# SAML21_Xplained_Pro_current_measurement_.net
KiCad netlist of a schematic drawn in Altium Designer
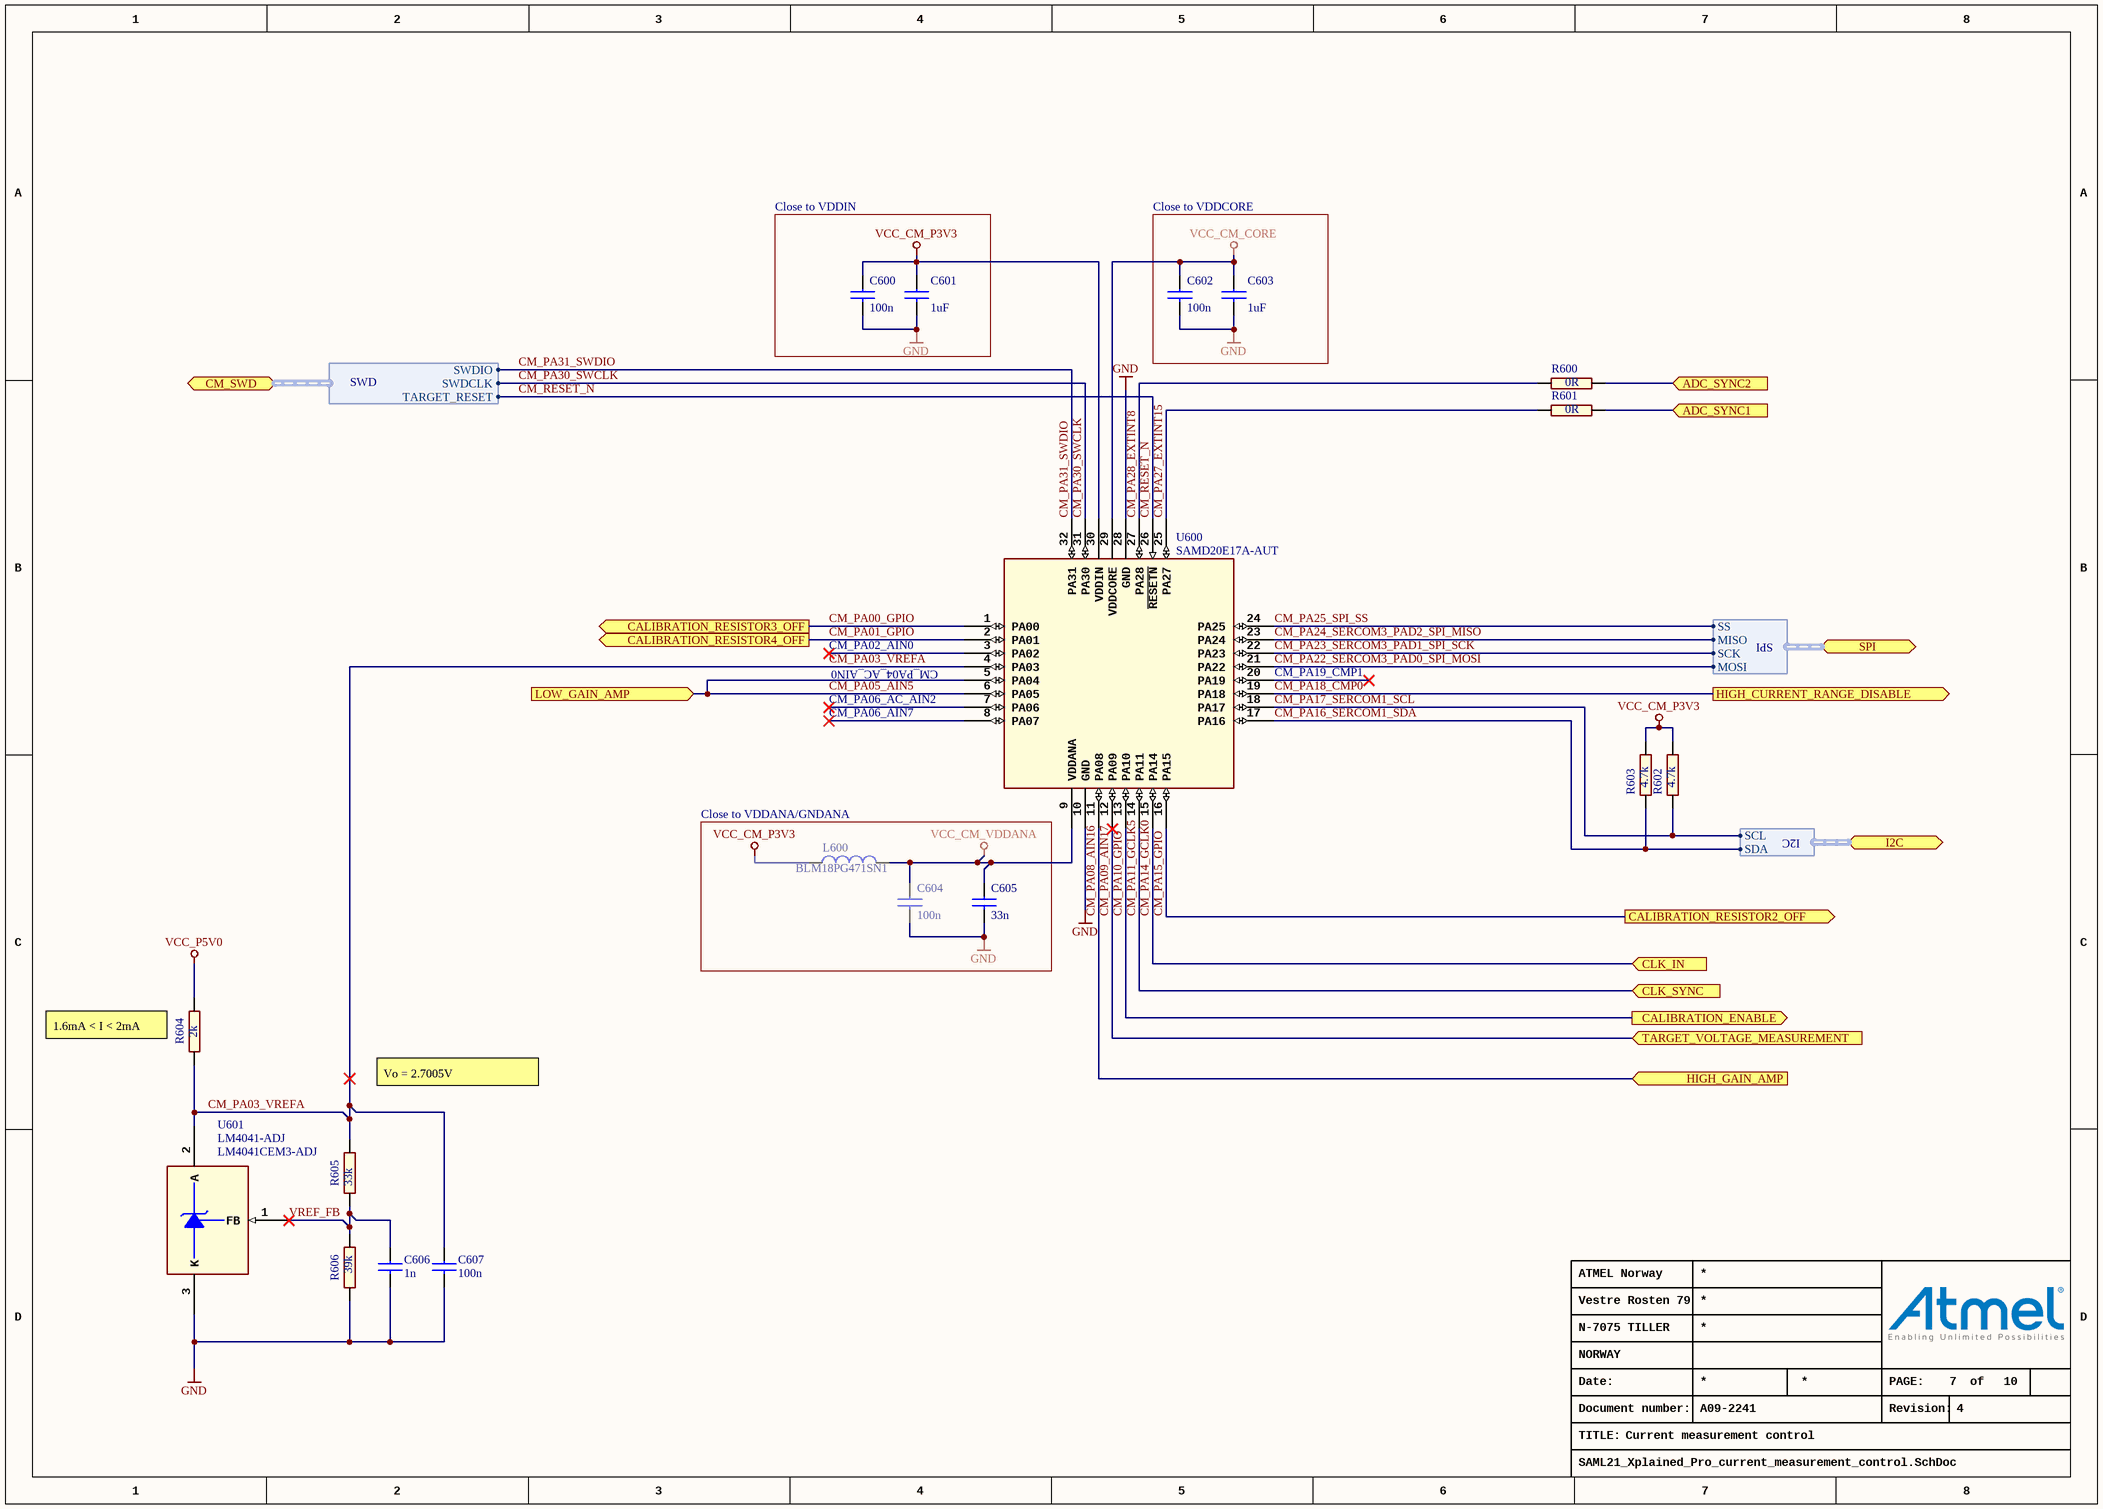
[diagram p0: SAML21_Xplained_Pro_current_measurement_control.SchDoc]

(export (version "E")
  (design (tool "Eeschema 10.0.6"))
  (components
    (comp (ref "C600")
      (value "100n")
      (footprint "AP1-00053")
      (description "Ceramic capacitor, SMD 0402, X7R, 16V, +/-10%")
      (fields (field (name "TOLERANCE") "16V, +/-10%") (field (name "MANUFACTURER") "Kemet"))
      (libsource (lib "AltiumDbLib") (part "CAP-NONPOL"))
    )
    (comp (ref "C601")
      (value "1uF")
      (footprint "AP1-00117")
      (description "Ceramic capacitor, SMD 0603, X5R, 25V, ±10%")
      (fields (field (name "TOLERANCE") "±10%") (field (name "MANUFACTURER") "Murata"))
      (libsource (lib "AltiumDbLib") (part "CAP-NONPOL"))
    )
    (comp (ref "C602")
      (value "100n")
      (footprint "AP1-00053")
      (description "Ceramic capacitor, SMD 0402, X7R, 16V, +/-10%")
      (fields (field (name "TOLERANCE") "16V, +/-10%") (field (name "MANUFACTURER") "Kemet"))
      (libsource (lib "AltiumDbLib") (part "CAP-NONPOL"))
    )
    (comp (ref "C603")
      (value "1uF")
      (footprint "AP1-00117")
      (description "Ceramic capacitor, SMD 0603, X5R, 25V, ±10%")
      (fields (field (name "TOLERANCE") "±10%") (field (name "MANUFACTURER") "Murata"))
      (libsource (lib "AltiumDbLib") (part "CAP-NONPOL"))
    )
    (comp (ref "C604")
      (value "100n")
      (footprint "AP1-00053")
      (description "Ceramic capacitor, SMD 0402, X7R, 16V, +/-10%")
      (fields (field (name "TOLERANCE") "16V, +/-10%") (field (name "MANUFACTURER") "Kemet"))
      (libsource (lib "AltiumDbLib") (part "CAP-NONPOL"))
    )
    (comp (ref "C605")
      (value "33n")
      (footprint "AP1-00053")
      (description "Ceramic capacitor, SMD 0402, X7R, 25V, ±10%")
      (fields (field (name "TOLERANCE") "±10%(K)") (field (name "MANUFACTURER") "Murata"))
      (libsource (lib "AltiumDbLib") (part "CAP-NONPOL"))
    )
    (comp (ref "C606")
      (value "1n")
      (footprint "AP1-00053")
      (description "Ceramic capacitor, SMD 0402, X7R, 50V, +/-10%")
      (fields (field (name "TOLERANCE") "50V, +/-10%") (field (name "Comment") "CAP-NONPOL"))
      (libsource (lib "AltiumDbLib") (part "CAP-NONPOL"))
    )
    (comp (ref "C607")
      (value "100n")
      (footprint "AP1-00053")
      (description "Ceramic capacitor, SMD 0402, X7R, 16V, +/-10%")
      (fields (field (name "TOLERANCE") "16V, +/-10%") (field (name "MANUFACTURER") "Kemet"))
      (libsource (lib "AltiumDbLib") (part "CAP-NONPOL"))
    )
    (comp (ref "L600")
      (value "BLM18PG471SN1")
      (footprint "AP3-00005")
      (description "SMD RF inductor 0603. Z=470Ohm (@100MHz), Max R(dc)=0.65Ohm, Max current=1A")
      (fields (field (name "TOLERANCE") "±25%") (field (name "MANUFACTURER") "Murata"))
      (libsource (lib "AltiumDbLib") (part "INDUCTOR"))
    )
    (comp (ref "R600")
      (value "0R")
      (footprint "AP2-00011")
      (description "RES 0.0 OHM 1/16W 0402 SMD")
      (fields (field (name "TOLERANCE") "1 %") (field (name "MANUFACTURER") "(n/a)"))
      (libsource (lib "") (part "R2_1"))
    )
    (comp (ref "R601")
      (value "0R")
      (footprint "AP2-00011")
      (description "RES 0.0 OHM 1/16W 0402 SMD")
      (fields (field (name "TOLERANCE") "1 %") (field (name "MANUFACTURER") "(n/a)"))
      (libsource (lib "") (part "R2_1"))
    )
    (comp (ref "R602")
      (value "4.7k")
      (footprint "AP2-00011")
      (description "Thick film resistor, SMD 0402, 1/16W, 1%")
      (fields (field (name "TOLERANCE") "1 %") (field (name "Comment") "R2"))
      (libsource (lib "") (part "R2_1"))
    )
    (comp (ref "R603")
      (value "4.7k")
      (footprint "AP2-00011")
      (description "Thick film resistor, SMD 0402, 1/16W, 1%")
      (fields (field (name "TOLERANCE") "1 %") (field (name "Comment") "R2"))
      (libsource (lib "") (part "R2_1"))
    )
    (comp (ref "R604")
      (value "2k")
      (footprint "AP2-00011")
      (description "Thick film resistor, SMD 0402, 1/16W, 1%")
      (fields (field (name "TOLERANCE") "1 %") (field (name "Comment") "R2"))
      (libsource (lib "AltiumDbLib") (part "R2"))
    )
    (comp (ref "R605")
      (value "33k")
      (footprint "AP2-00011")
      (description "Thick film resistor, SMD 0402, 1/16W, 1%")
      (fields (field (name "TOLERANCE") "1 %") (field (name "Comment") "R2"))
      (libsource (lib "AltiumDbLib") (part "R2"))
    )
    (comp (ref "R606")
      (value "39k")
      (footprint "AP2-00011")
      (description "Thick film resistor, SMD 0402, 1/16W, 1%")
      (fields (field (name "TOLERANCE") "1 %") (field (name "Comment") "R2"))
      (libsource (lib "AltiumDbLib") (part "R2"))
    )
    (comp (ref "U600")
      (value "SAMD20E17A-AUT")
      (footprint "AP6-00061")
      (description "Atmel 32bit RISC MCU 32 pin")
      (fields (field (name "MANUFACTURER") "ATMEL") (field (name "MPN") "ATSAMD20E17A-AUT"))
      (libsource (lib "AltiumDbLib") (part "SAMD20E"))
    )
    (comp (ref "U601")
      (value "LM4041-ADJ")
      (footprint "AP5-00002")
      (description "Adjustable shunt voltage regulator, 1.24 to 10V out")
      (fields
        (field (name "ALTIUM_VALUE") "LM4041CEM3-ADJ")
        (field (name "MANUFACTURER") "National Semiconductor")
        (field (name "MPN") "LM4041CEM3-ADJ")
      )
      (libsource (lib "AltiumDbLib") (part "LM4041-ADJ"))
    )
  )
  (nets
    (net (code "4") (name "/ADC_SYNC1") (class "Default")
      (node (ref "R601") (pin "2") (pinfunction "2_2") (pintype "passive"))
    )
    (net (code "5") (name "/ADC_SYNC2") (class "Default")
      (node (ref "R600") (pin "2") (pinfunction "2_2") (pintype "passive"))
    )
    (net (code "6") (name "/CM_PA00_GPIO") (class "Default")
      (node (ref "U600") (pin "1") (pinfunction "PA00_1") (pintype "bidirectional"))
    )
    (net (code "7") (name "/CM_PA01_GPIO") (class "Default")
      (node (ref "U600") (pin "2") (pinfunction "PA01_2") (pintype "bidirectional"))
    )
    (net (code "8") (name "/CM_PA03_VREFA") (class "Default")
      (node (ref "C607") (pin "1") (pinfunction "1_1") (pintype "passive"))
      (node (ref "R604") (pin "1") (pinfunction "1_1") (pintype "passive"))
      (node (ref "R605") (pin "2") (pinfunction "2_2") (pintype "passive"))
      (node (ref "U600") (pin "4") (pinfunction "PA03_4") (pintype "bidirectional"))
      (node (ref "U601") (pin "2") (pinfunction "A_2") (pintype "power_in"))
    )
    (net (code "9") (name "/CM_PA05_AIN5") (class "Default")
      (node (ref "U600") (pin "5") (pinfunction "PA04_5") (pintype "bidirectional"))
      (node (ref "U600") (pin "6") (pinfunction "PA05_6") (pintype "bidirectional"))
    )
    (net (code "10") (name "/CM_PA08_AIN16") (class "Default")
      (node (ref "U600") (pin "11") (pinfunction "PA08_11") (pintype "bidirectional"))
    )
    (net (code "11") (name "/CM_PA09_AIN17") (class "Default")
      (node (ref "U600") (pin "12") (pinfunction "PA09_12") (pintype "bidirectional+no_connect"))
    )
    (net (code "12") (name "/CM_PA10_GPIO") (class "Default")
      (node (ref "U600") (pin "13") (pinfunction "PA10_13") (pintype "bidirectional"))
    )
    (net (code "13") (name "/CM_PA11_GCLK5") (class "Default")
      (node (ref "U600") (pin "14") (pinfunction "PA11_14") (pintype "bidirectional"))
    )
    (net (code "14") (name "/CM_PA14_GCLK0") (class "Default")
      (node (ref "U600") (pin "15") (pinfunction "PA14_15") (pintype "bidirectional"))
    )
    (net (code "15") (name "/CM_PA15_GPIO") (class "Default")
      (node (ref "U600") (pin "16") (pinfunction "PA15_16") (pintype "bidirectional"))
    )
    (net (code "16") (name "/CM_PA16_SERCOM1_SDA") (class "Default")
      (node (ref "R603") (pin "1") (pinfunction "1_1") (pintype "passive"))
      (node (ref "U600") (pin "17") (pinfunction "PA16_17") (pintype "bidirectional"))
    )
    (net (code "17") (name "/CM_PA17_SERCOM1_SCL") (class "Default")
      (node (ref "R602") (pin "1") (pinfunction "1_1") (pintype "passive"))
      (node (ref "U600") (pin "18") (pinfunction "PA17_18") (pintype "bidirectional"))
    )
    (net (code "18") (name "/CM_PA18_CMP0") (class "Default")
      (node (ref "U600") (pin "19") (pinfunction "PA18_19") (pintype "bidirectional"))
    )
    (net (code "19") (name "/CM_PA22_SERCOM3_PAD0_SPI_MOSI") (class "Default")
      (node (ref "U600") (pin "21") (pinfunction "PA22_21") (pintype "bidirectional"))
    )
    (net (code "20") (name "/CM_PA23_SERCOM3_PAD1_SPI_SCK") (class "Default")
      (node (ref "U600") (pin "22") (pinfunction "PA23_22") (pintype "bidirectional"))
    )
    (net (code "21") (name "/CM_PA24_SERCOM3_PAD2_SPI_MISO") (class "Default")
      (node (ref "U600") (pin "23") (pinfunction "PA24_23") (pintype "bidirectional"))
    )
    (net (code "22") (name "/CM_PA25_SPI_SS") (class "Default")
      (node (ref "U600") (pin "24") (pinfunction "PA25_24") (pintype "bidirectional"))
    )
    (net (code "23") (name "/CM_PA27_EXTINT15") (class "Default")
      (node (ref "R601") (pin "1") (pinfunction "1_1") (pintype "passive"))
      (node (ref "U600") (pin "25") (pinfunction "PA27_25") (pintype "bidirectional"))
    )
    (net (code "24") (name "/CM_PA28_EXTINT8") (class "Default")
      (node (ref "R600") (pin "1") (pinfunction "1_1") (pintype "passive"))
      (node (ref "U600") (pin "27") (pinfunction "PA28_27") (pintype "bidirectional"))
    )
    (net (code "25") (name "/CM_PA30_SWCLK") (class "Default")
      (node (ref "U600") (pin "31") (pinfunction "PA30_31") (pintype "bidirectional"))
    )
    (net (code "26") (name "/CM_PA31_SWDIO") (class "Default")
      (node (ref "U600") (pin "32") (pinfunction "PA31_32") (pintype "bidirectional"))
    )
    (net (code "27") (name "/CM_RESET_N") (class "Default")
      (node (ref "U600") (pin "26") (pinfunction "~{RESETN}_26") (pintype "input"))
    )
    (net (code "28") (name "/VREF_FB") (class "Default")
      (node (ref "C606") (pin "1") (pinfunction "1_1") (pintype "passive"))
      (node (ref "R605") (pin "1") (pinfunction "1_1") (pintype "passive"))
      (node (ref "R606") (pin "2") (pinfunction "2_2") (pintype "passive"))
      (node (ref "U601") (pin "1") (pinfunction "FB_1") (pintype "input"))
    )
    (net (code "32") (name "GND") (class "Default")
      (node (ref "C600") (pin "2") (pinfunction "2_2") (pintype "passive"))
      (node (ref "C601") (pin "2") (pinfunction "2_2") (pintype "passive"))
      (node (ref "C602") (pin "2") (pinfunction "2_2") (pintype "passive"))
      (node (ref "C603") (pin "2") (pinfunction "2_2") (pintype "passive"))
      (node (ref "C604") (pin "2") (pinfunction "2_2") (pintype "passive"))
      (node (ref "C605") (pin "2") (pinfunction "2_2") (pintype "passive"))
      (node (ref "C606") (pin "2") (pinfunction "2_2") (pintype "passive"))
      (node (ref "C607") (pin "2") (pinfunction "2_2") (pintype "passive"))
      (node (ref "R606") (pin "1") (pinfunction "1_1") (pintype "passive"))
      (node (ref "U600") (pin "10") (pinfunction "GND_10") (pintype "power_in"))
      (node (ref "U600") (pin "28") (pinfunction "GND_28") (pintype "power_in"))
      (node (ref "U601") (pin "3") (pinfunction "K_3") (pintype "power_in"))
    )
    (net (code "33") (name "VCC_CM_CORE") (class "Default")
      (node (ref "C602") (pin "1") (pinfunction "1_1") (pintype "passive"))
      (node (ref "C603") (pin "1") (pinfunction "1_1") (pintype "passive"))
      (node (ref "U600") (pin "29") (pinfunction "VDDCORE_29") (pintype "power_in"))
    )
    (net (code "34") (name "VCC_CM_P3V3") (class "Default")
      (node (ref "C600") (pin "1") (pinfunction "1_1") (pintype "passive"))
      (node (ref "C601") (pin "1") (pinfunction "1_1") (pintype "passive"))
      (node (ref "L600") (pin "1") (pinfunction "1_1") (pintype "passive"))
      (node (ref "R602") (pin "2") (pinfunction "2_2") (pintype "passive"))
      (node (ref "R603") (pin "2") (pinfunction "2_2") (pintype "passive"))
      (node (ref "U600") (pin "30") (pinfunction "VDDIN_30") (pintype "power_in"))
    )
    (net (code "35") (name "VCC_CM_VDDANA") (class "Default")
      (node (ref "C604") (pin "1") (pinfunction "1_1") (pintype "passive"))
      (node (ref "C605") (pin "1") (pinfunction "1_1") (pintype "passive"))
      (node (ref "L600") (pin "2") (pinfunction "2_2") (pintype "passive"))
      (node (ref "U600") (pin "9") (pinfunction "VDDANA_9") (pintype "power_in"))
    )
    (net (code "36") (name "VCC_P5V0") (class "Default")
      (node (ref "R604") (pin "2") (pinfunction "2_2") (pintype "passive"))
    )
    (net (code "37") (name "unconnected-(U600-PA02-Pad3)") (class "Default")
      (node (ref "U600") (pin "3") (pinfunction "PA02_3") (pintype "bidirectional+no_connect"))
    )
    (net (code "38") (name "unconnected-(U600-PA06-Pad7)") (class "Default")
      (node (ref "U600") (pin "7") (pinfunction "PA06_7") (pintype "bidirectional+no_connect"))
    )
    (net (code "39") (name "unconnected-(U600-PA07-Pad8)") (class "Default")
      (node (ref "U600") (pin "8") (pinfunction "PA07_8") (pintype "bidirectional+no_connect"))
    )
    (net (code "40") (name "unconnected-(U600-PA19-Pad20)") (class "Default")
      (node (ref "U600") (pin "20") (pinfunction "PA19_20") (pintype "bidirectional+no_connect"))
    )
  )
)
